# Forward_Active_Supply.net
KiCad netlist of a schematic drawn in Altium Designer
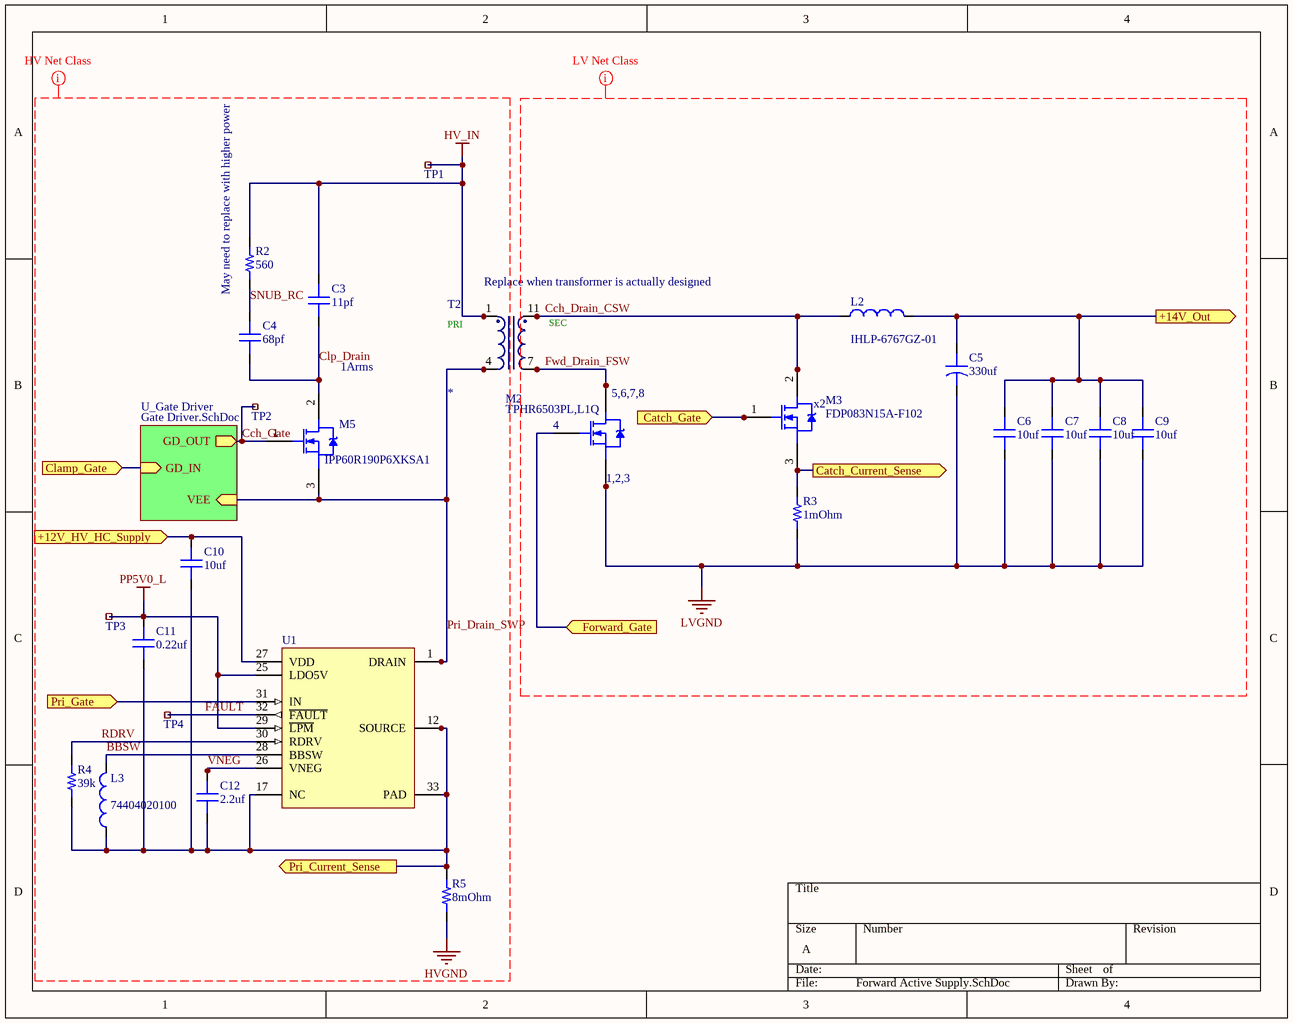
[diagram p0: Forward Active Supply.SchDoc]

(export (version "E")
  (design (tool "Eeschema 10.0.6"))
  (components
    (comp (ref "C3")
      (value "11pf")
      (footprint "CAP 0805/2012")
      (fields
        (field (name "TOLERANCE") "2%")
        (field (name "Comment") "Capacitor MLCC 11pf 250V CAP 0805/2012")
        (field (name "CREATED_BY") "Nick Mah")
      )
      (libsource (lib "Altium-Lib") (part "Capacitor"))
    )
    (comp (ref "C4")
      (value "68pf")
      (footprint "CAP 0805/2012")
      (fields
        (field (name "TOLERANCE") "5%")
        (field (name "Comment") "Capacitor MLCC 68pf 200V CAP 0805/2012")
        (field (name "CREATED_BY") "Nick Mah")
      )
      (libsource (lib "Altium-Lib") (part "Capacitor"))
    )
    (comp (ref "C5")
      (value "330uf")
      (footprint "CAP ALUM 8.3MM")
      (description "Null")
      (fields
        (field (name "TOLERANCE") "20%")
        (field (name "MFRPARTNO") "EEH-ZA1E221P")
        (field (name "CREATED_BY") "Jason Zhou")
        (field (name "UPDATED_BY") "Jason Zhou")
      )
      (libsource (lib "Altium-Lib") (part "Capacitor_Electrolytic"))
    )
    (comp (ref "C6")
      (value "10uf")
      (footprint "CAP 1206/3216 - 1.8MM")
      (fields
        (field (name "TOLERANCE") "10%")
        (field (name "MFRPARTNO") "C3216X7R1E106K160AB")
        (field (name "Comment") "Capacitor MLCC 10uf 25V CAP 1206/3216")
        (field (name "CREATED_BY") "Jason Zhou")
      )
      (libsource (lib "Altium-Lib") (part "Capacitor"))
    )
    (comp (ref "C7")
      (value "10uf")
      (footprint "CAP 1206/3216 - 1.8MM")
      (fields
        (field (name "TOLERANCE") "10%")
        (field (name "MFRPARTNO") "C3216X7R1E106K160AB")
        (field (name "Comment") "Capacitor MLCC 10uf 25V CAP 1206/3216")
        (field (name "CREATED_BY") "Jason Zhou")
      )
      (libsource (lib "Altium-Lib") (part "Capacitor"))
    )
    (comp (ref "C8")
      (value "10uf")
      (footprint "CAP 1206/3216 - 1.8MM")
      (fields
        (field (name "TOLERANCE") "10%")
        (field (name "MFRPARTNO") "C3216X7R1E106K160AB")
        (field (name "Comment") "Capacitor MLCC 10uf 25V CAP 1206/3216")
        (field (name "CREATED_BY") "Jason Zhou")
      )
      (libsource (lib "Altium-Lib") (part "Capacitor"))
    )
    (comp (ref "C9")
      (value "10uf")
      (footprint "CAP 1206/3216 - 1.8MM")
      (fields
        (field (name "TOLERANCE") "10%")
        (field (name "MFRPARTNO") "C3216X7R1E106K160AB")
        (field (name "Comment") "Capacitor MLCC 10uf 25V CAP 1206/3216")
        (field (name "CREATED_BY") "Jason Zhou")
      )
      (libsource (lib "Altium-Lib") (part "Capacitor"))
    )
    (comp (ref "C10")
      (value "10uf")
      (footprint "CAP 0603/1608")
      (fields
        (field (name "Comment") "Capacitor MLCC 10uf 16V CAP 0603/1608")
        (field (name "CREATED_BY") "Nick Mah")
      )
      (libsource (lib "Altium-Lib") (part "Capacitor"))
    )
    (comp (ref "C11")
      (value "0.22uf")
      (footprint "CAP 0603/1608")
      (fields
        (field (name "Comment") "Capacitor MLCC 0.22uf 50V CAP 0603/1608")
        (field (name "CREATED_BY") "Nick Mah")
      )
      (libsource (lib "Altium-Lib") (part "Capacitor"))
    )
    (comp (ref "C12")
      (value "2.2uf")
      (footprint "CAP 0603/1608")
      (fields
        (field (name "Comment") "Capacitor MLCC 2.2uf 25V CAP 0603/1608")
        (field (name "CREATED_BY") "Nick Mah")
      )
      (libsource (lib "Altium-Lib") (part "Capacitor"))
    )
    (comp (ref "L2")
      (value "~")
      (footprint "IHLP-6767GZ")
      (description "1.5µH Shielded Molded Inductor 42A 1.88mOhm Max Nonstandard")
      (fields
        (field (name "MFRPARTNO") "IHLP-6767GZ-01")
        (field (name "TOLERANCE") "20%")
        (field (name "CREATED_BY") "Jason Zhou")
      )
      (libsource (lib "Altium-Lib") (part "Inductor"))
    )
    (comp (ref "L3")
      (value "~")
      (footprint "74404020100")
      (description "10µH Shielded Wirewound Inductor 500mA 850mOhm Nonstandard")
      (fields
        (field (name "MFRPARTNO") "74404020100")
        (field (name "TOLERANCE") "20%")
        (field (name "CREATED_BY") "Jason Zhou")
      )
      (libsource (lib "Altium-Lib") (part "Inductor"))
    )
    (comp (ref "M2")
      (value "Forward Mosfet")
      (footprint "SOP Advance")
      (description "N-Channel 30V 150A (Tc) 960mW (Ta), 170W (Tc) Surface Mount 8-SOP Advance (5x5)")
      (fields (field (name "MFRPARTNO") "TPHR6503PL,L1Q") (field (name "CREATED_BY") "Nick Mah"))
      (libsource (lib "Altium-Lib") (part "TPHR6503PL"))
    )
    (comp (ref "M3")
      (value "Catch Mosfet x2")
      (footprint "TO-220ABx2")
      (description "N-Channel 150V 83A (Tc) 294W (Tc) Through Hole TO-220-3")
      (fields (field (name "MFRPARTNO") "FDP083N15A-F102"))
      (libsource (lib "Altium-Lib") (part "FDP083N15Ax2"))
    )
    (comp (ref "M5")
      (value "Clamp Transistor")
      (footprint "IPP60R190P6")
      (description "N-Channel 600V 20.2A (Tc) 151W (Tc) Through Hole PG-TO220-3")
      (fields (field (name "MFRPARTNO") "IPP60R190P6XKSA1") (field (name "CREATED_BY") "Nick Mah"))
      (libsource (lib "Altium-Lib") (part "IPP60R190P6"))
    )
    (comp (ref "R2")
      (value "560")
      (footprint "RES 1206/3216")
      (fields
        (field (name "TOLERANCE") "5%")
        (field (name "POWER") "1W")
        (field (name "Comment") "RES 560 OHM 1% 1W 1206")
        (field (name "CREATED_BY") "Nick Mah")
      )
      (libsource (lib "Altium-Lib") (part "Resistor"))
    )
    (comp (ref "R3")
      (value "1mOhm")
      (footprint "RES 2010/5025")
      (description "1 mOhms ±1% 1.5W Chip Resistor 2010 (5025 Metric) Current Sense, Moisture Resistant Metal Foil")
      (fields
        (field (name "TOLERANCE") "1%")
        (field (name "POWER") "1.5W")
        (field (name "CREATED_BY") "Nick Mah")
      )
      (libsource (lib "Altium-Lib") (part "Resistor"))
    )
    (comp (ref "R4")
      (value "39k")
      (footprint "RES 0603/1608")
      (fields
        (field (name "TOLERANCE") "1%")
        (field (name "POWER") "1/10W")
        (field (name "Comment") "Resistor 39k 0603 1/10W 1%")
        (field (name "CREATED_BY") "Nick Mah")
      )
      (libsource (lib "Altium-Lib") (part "Resistor"))
    )
    (comp (ref "R5")
      (value "8mOhm")
      (footprint "RES 1206/3216")
      (description "8 mOhms ±1% 1W Chip Resistor 1206 (3216 Metric) Automotive AEC-Q200, Current Sense Thick Film")
      (fields
        (field (name "TOLERANCE") "1%")
        (field (name "POWER") "1W")
        (field (name "CREATED_BY") "Nick Mah")
      )
      (libsource (lib "Altium-Lib") (part "Resistor"))
    )
    (comp (ref "T2")
      (value "~")
      (footprint "B66359")
      (fields (field (name "MFRPARTNO") "*"))
      (libsource (lib "Altium-Lib") (part "B66359"))
    )
    (comp (ref "TP1")
      (value "RCU-0C")
      (footprint "5029")
      (description "Test point")
      (fields
        (field (name "MFRPARTNO") "5029")
        (field (name "COMPONENTLINK1URL") "file:///C:/Users/Jason%20Zhou/Downloads/5029.PDF")
        (field (name "CREATED_BY") "Jason Zhou")
      )
      (libsource (lib "Altium-Lib") (part "RCU-0C"))
    )
    (comp (ref "TP2")
      (value "RCU-0C")
      (footprint "5029")
      (description "Test point")
      (fields
        (field (name "MFRPARTNO") "5029")
        (field (name "COMPONENTLINK1URL") "file:///C:/Users/Jason%20Zhou/Downloads/5029.PDF")
        (field (name "CREATED_BY") "Jason Zhou")
      )
      (libsource (lib "Altium-Lib") (part "RCU-0C"))
    )
    (comp (ref "TP3")
      (value "RCU-0C")
      (footprint "5029")
      (description "Test point")
      (fields
        (field (name "MFRPARTNO") "5029")
        (field (name "COMPONENTLINK1URL") "file:///C:/Users/Jason%20Zhou/Downloads/5029.PDF")
        (field (name "CREATED_BY") "Jason Zhou")
      )
      (libsource (lib "Altium-Lib") (part "RCU-0C"))
    )
    (comp (ref "TP4")
      (value "RCU-0C")
      (footprint "5029")
      (description "Test point")
      (fields
        (field (name "MFRPARTNO") "5029")
        (field (name "COMPONENTLINK1URL") "file:///C:/Users/Jason%20Zhou/Downloads/5029.PDF")
        (field (name "CREATED_BY") "Jason Zhou")
      )
      (libsource (lib "Altium-Lib") (part "RCU-0C"))
    )
    (comp (ref "U1")
      (value "~")
      (footprint "RWH0032A")
      (description "N-Channel 600-V 50mOhm GaN with integrated driver and protection")
      (fields (field (name "MFRPARTNO") "XLMG3410R050RWHT") (field (name "CREATED_BY") "Jason Zhou"))
      (libsource (lib "Altium-Lib") (part "LMG3410R050"))
    )
  )
  (nets
    (net (code "1") (name "/+12V_HV_HC_Supply") (class "Default")
      (node (ref "C10") (pin "2") (pinfunction "2_2") (pintype "passive"))
      (node (ref "U1") (pin "27") (pinfunction "VDD_27") (pintype "power_in"))
    )
    (net (code "2") (name "/+14V_Out") (class "Default")
      (node (ref "C5") (pin "1") (pinfunction "1_1") (pintype "passive"))
      (node (ref "C6") (pin "2") (pinfunction "2_2") (pintype "passive"))
      (node (ref "C7") (pin "2") (pinfunction "2_2") (pintype "passive"))
      (node (ref "C8") (pin "2") (pinfunction "2_2") (pintype "passive"))
      (node (ref "C9") (pin "2") (pinfunction "2_2") (pintype "passive"))
      (node (ref "L2") (pin "2") (pinfunction "2_2") (pintype "passive"))
    )
    (net (code "3") (name "/BBSW") (class "Default")
      (node (ref "L3") (pin "2") (pinfunction "2_2") (pintype "passive"))
      (node (ref "U1") (pin "28") (pinfunction "BBSW_28") (pintype "power_in"))
    )
    (net (code "4") (name "/Catch_Current_Sense") (class "Default")
      (node (ref "M3") (pin "3") (pinfunction "S_3") (pintype "passive"))
      (node (ref "M3") (pin "6") (pinfunction "S_6") (pintype "passive"))
      (node (ref "R3") (pin "2") (pinfunction "2_2") (pintype "passive"))
    )
    (net (code "5") (name "/Catch_Gate") (class "Default")
      (node (ref "M3") (pin "1") (pinfunction "G_1") (pintype "passive"))
      (node (ref "M3") (pin "4") (pinfunction "G_4") (pintype "passive"))
    )
    (net (code "6") (name "/Cch_Drain_CSW") (class "Default")
      (node (ref "L2") (pin "1") (pinfunction "1_1") (pintype "passive"))
      (node (ref "M3") (pin "2") (pinfunction "D_2") (pintype "passive"))
      (node (ref "M3") (pin "5") (pinfunction "D_5") (pintype "passive"))
      (node (ref "T2") (pin "11") (pinfunction "11_11") (pintype "power_in"))
      (node (ref "T2") (pin "12") (pinfunction "12_12") (pintype "power_in"))
      (node (ref "T2") (pin "13") (pinfunction "13_13") (pintype "power_in"))
    )
    (net (code "7") (name "/Cch_Gate") (class "Default")
      (node (ref "M5") (pin "1") (pinfunction "G_1") (pintype "passive"))
      (node (ref "TP2") (pin "1") (pintype "passive"))
    )
    (net (code "9") (name "/Clp_Drain") (class "Default")
      (node (ref "C3") (pin "1") (pinfunction "1_1") (pintype "passive"))
      (node (ref "C4") (pin "1") (pinfunction "1_1") (pintype "passive"))
      (node (ref "M5") (pin "2") (pinfunction "D_2") (pintype "passive"))
    )
    (net (code "10") (name "/FAULT") (class "Default")
      (node (ref "TP4") (pin "1") (pintype "passive"))
      (node (ref "U1") (pin "32") (pinfunction "~{FAULT}_32") (pintype "output"))
    )
    (net (code "11") (name "/Forward_Gate") (class "Default")
      (node (ref "M2") (pin "4") (pinfunction "G_4") (pintype "passive"))
    )
    (net (code "12") (name "/Fwd_Drain_FSW") (class "Default")
      (node (ref "M2") (pin "5") (pinfunction "D_5") (pintype "passive"))
      (node (ref "M2") (pin "6") (pinfunction "D_6") (pintype "passive"))
      (node (ref "M2") (pin "7") (pinfunction "D_7") (pintype "passive"))
      (node (ref "M2") (pin "8") (pinfunction "D_8") (pintype "passive"))
      (node (ref "T2") (pin "10") (pinfunction "10_10") (pintype "power_in"))
      (node (ref "T2") (pin "7") (pinfunction "7_7") (pintype "power_in"))
      (node (ref "T2") (pin "8") (pinfunction "8_8") (pintype "power_in"))
      (node (ref "T2") (pin "9") (pinfunction "9_9") (pintype "power_in"))
    )
    (net (code "13") (name "/Pri_Current_Sense") (class "Default")
      (node (ref "C10") (pin "1") (pinfunction "1_1") (pintype "passive"))
      (node (ref "C11") (pin "1") (pinfunction "1_1") (pintype "passive"))
      (node (ref "C12") (pin "2") (pinfunction "2_2") (pintype "passive"))
      (node (ref "L3") (pin "1") (pinfunction "1_1") (pintype "passive"))
      (node (ref "R4") (pin "1") (pinfunction "1_1") (pintype "passive"))
      (node (ref "R5") (pin "2") (pinfunction "2_2") (pintype "passive"))
      (node (ref "U1") (pin "12") (pinfunction "SOURCE_12") (pintype "power_in"))
      (node (ref "U1") (pin "13") (pinfunction "SOURCE_13") (pintype "power_in"))
      (node (ref "U1") (pin "14") (pinfunction "SOURCE_14") (pintype "power_in"))
      (node (ref "U1") (pin "15") (pinfunction "SOURCE_15") (pintype "power_in"))
      (node (ref "U1") (pin "16") (pinfunction "SOURCE_16") (pintype "power_in"))
      (node (ref "U1") (pin "17") (pinfunction "NC_17") (pintype "tri_state"))
      (node (ref "U1") (pin "18") (pinfunction "SOURCE_18") (pintype "power_in"))
      (node (ref "U1") (pin "19") (pinfunction "SOURCE_19") (pintype "power_in"))
      (node (ref "U1") (pin "20") (pinfunction "SOURCE_20") (pintype "power_in"))
      (node (ref "U1") (pin "21") (pinfunction "SOURCE_21") (pintype "power_in"))
      (node (ref "U1") (pin "22") (pinfunction "SOURCE_22") (pintype "power_in"))
      (node (ref "U1") (pin "23") (pinfunction "SOURCE_23") (pintype "power_in"))
      (node (ref "U1") (pin "24") (pinfunction "SOURCE_24") (pintype "power_in"))
      (node (ref "U1") (pin "33") (pinfunction "PAD_33") (pintype "power_in"))
    )
    (net (code "14") (name "/Pri_Drain_SWP") (class "Default")
      (node (ref "M5") (pin "3") (pinfunction "S_3") (pintype "passive"))
      (node (ref "T2") (pin "4") (pinfunction "4_4") (pintype "passive"))
      (node (ref "T2") (pin "5") (pinfunction "5_5") (pintype "power_in"))
      (node (ref "T2") (pin "6") (pinfunction "6_6") (pintype "power_in"))
      (node (ref "U1") (pin "1") (pinfunction "DRAIN_1") (pintype "power_in"))
      (node (ref "U1") (pin "10") (pinfunction "DRAIN_10") (pintype "power_in"))
      (node (ref "U1") (pin "11") (pinfunction "DRAIN_11") (pintype "power_in"))
      (node (ref "U1") (pin "2") (pinfunction "DRAIN_2") (pintype "power_in"))
      (node (ref "U1") (pin "3") (pinfunction "DRAIN_3") (pintype "power_in"))
      (node (ref "U1") (pin "4") (pinfunction "DRAIN_4") (pintype "power_in"))
      (node (ref "U1") (pin "5") (pinfunction "DRAIN_5") (pintype "power_in"))
      (node (ref "U1") (pin "6") (pinfunction "DRAIN_6") (pintype "power_in"))
      (node (ref "U1") (pin "7") (pinfunction "DRAIN_7") (pintype "power_in"))
      (node (ref "U1") (pin "8") (pinfunction "DRAIN_8") (pintype "power_in"))
      (node (ref "U1") (pin "9") (pinfunction "DRAIN_9") (pintype "power_in"))
    )
    (net (code "15") (name "/Pri_Gate") (class "Default")
      (node (ref "U1") (pin "31") (pinfunction "IN_31") (pintype "input"))
    )
    (net (code "16") (name "/RDRV") (class "Default")
      (node (ref "R4") (pin "2") (pinfunction "2_2") (pintype "passive"))
      (node (ref "U1") (pin "30") (pinfunction "RDRV_30") (pintype "input"))
    )
    (net (code "17") (name "/SNUB_RC") (class "Default")
      (node (ref "C4") (pin "2") (pinfunction "2_2") (pintype "passive"))
      (node (ref "R2") (pin "1") (pinfunction "1_1") (pintype "passive"))
    )
    (net (code "18") (name "/VNEG") (class "Default")
      (node (ref "C12") (pin "1") (pinfunction "1_1") (pintype "passive"))
      (node (ref "U1") (pin "26") (pinfunction "VNEG_26") (pintype "power_in"))
    )
    (net (code "19") (name "HVGND") (class "Default")
      (node (ref "R5") (pin "1") (pinfunction "1_1") (pintype "passive"))
    )
    (net (code "20") (name "HV_IN") (class "Default")
      (node (ref "C3") (pin "2") (pinfunction "2_2") (pintype "passive"))
      (node (ref "R2") (pin "2") (pinfunction "2_2") (pintype "passive"))
      (node (ref "T2") (pin "1") (pinfunction "1_1") (pintype "passive"))
      (node (ref "T2") (pin "2") (pinfunction "2_2") (pintype "passive"))
      (node (ref "T2") (pin "3") (pinfunction "3_3") (pintype "passive"))
      (node (ref "TP1") (pin "1") (pintype "passive"))
    )
    (net (code "21") (name "LVGND") (class "Default")
      (node (ref "C5") (pin "2") (pinfunction "2_2") (pintype "passive"))
      (node (ref "C6") (pin "1") (pinfunction "1_1") (pintype "passive"))
      (node (ref "C7") (pin "1") (pinfunction "1_1") (pintype "passive"))
      (node (ref "C8") (pin "1") (pinfunction "1_1") (pintype "passive"))
      (node (ref "C9") (pin "1") (pinfunction "1_1") (pintype "passive"))
      (node (ref "M2") (pin "1") (pinfunction "S_1") (pintype "passive"))
      (node (ref "M2") (pin "2") (pinfunction "S_2") (pintype "passive"))
      (node (ref "M2") (pin "3") (pinfunction "S_3") (pintype "passive"))
      (node (ref "R3") (pin "1") (pinfunction "1_1") (pintype "passive"))
    )
    (net (code "22") (name "PP5V0_L") (class "Default")
      (node (ref "C11") (pin "2") (pinfunction "2_2") (pintype "passive"))
      (node (ref "TP3") (pin "1") (pintype "passive"))
      (node (ref "U1") (pin "25") (pinfunction "LDO5V_25") (pintype "power_in"))
      (node (ref "U1") (pin "29") (pinfunction "~{LPM}_29") (pintype "input"))
    )
  )
)
